# source_eagle.net
KiCad netlist of a schematic drawn in EAGLE
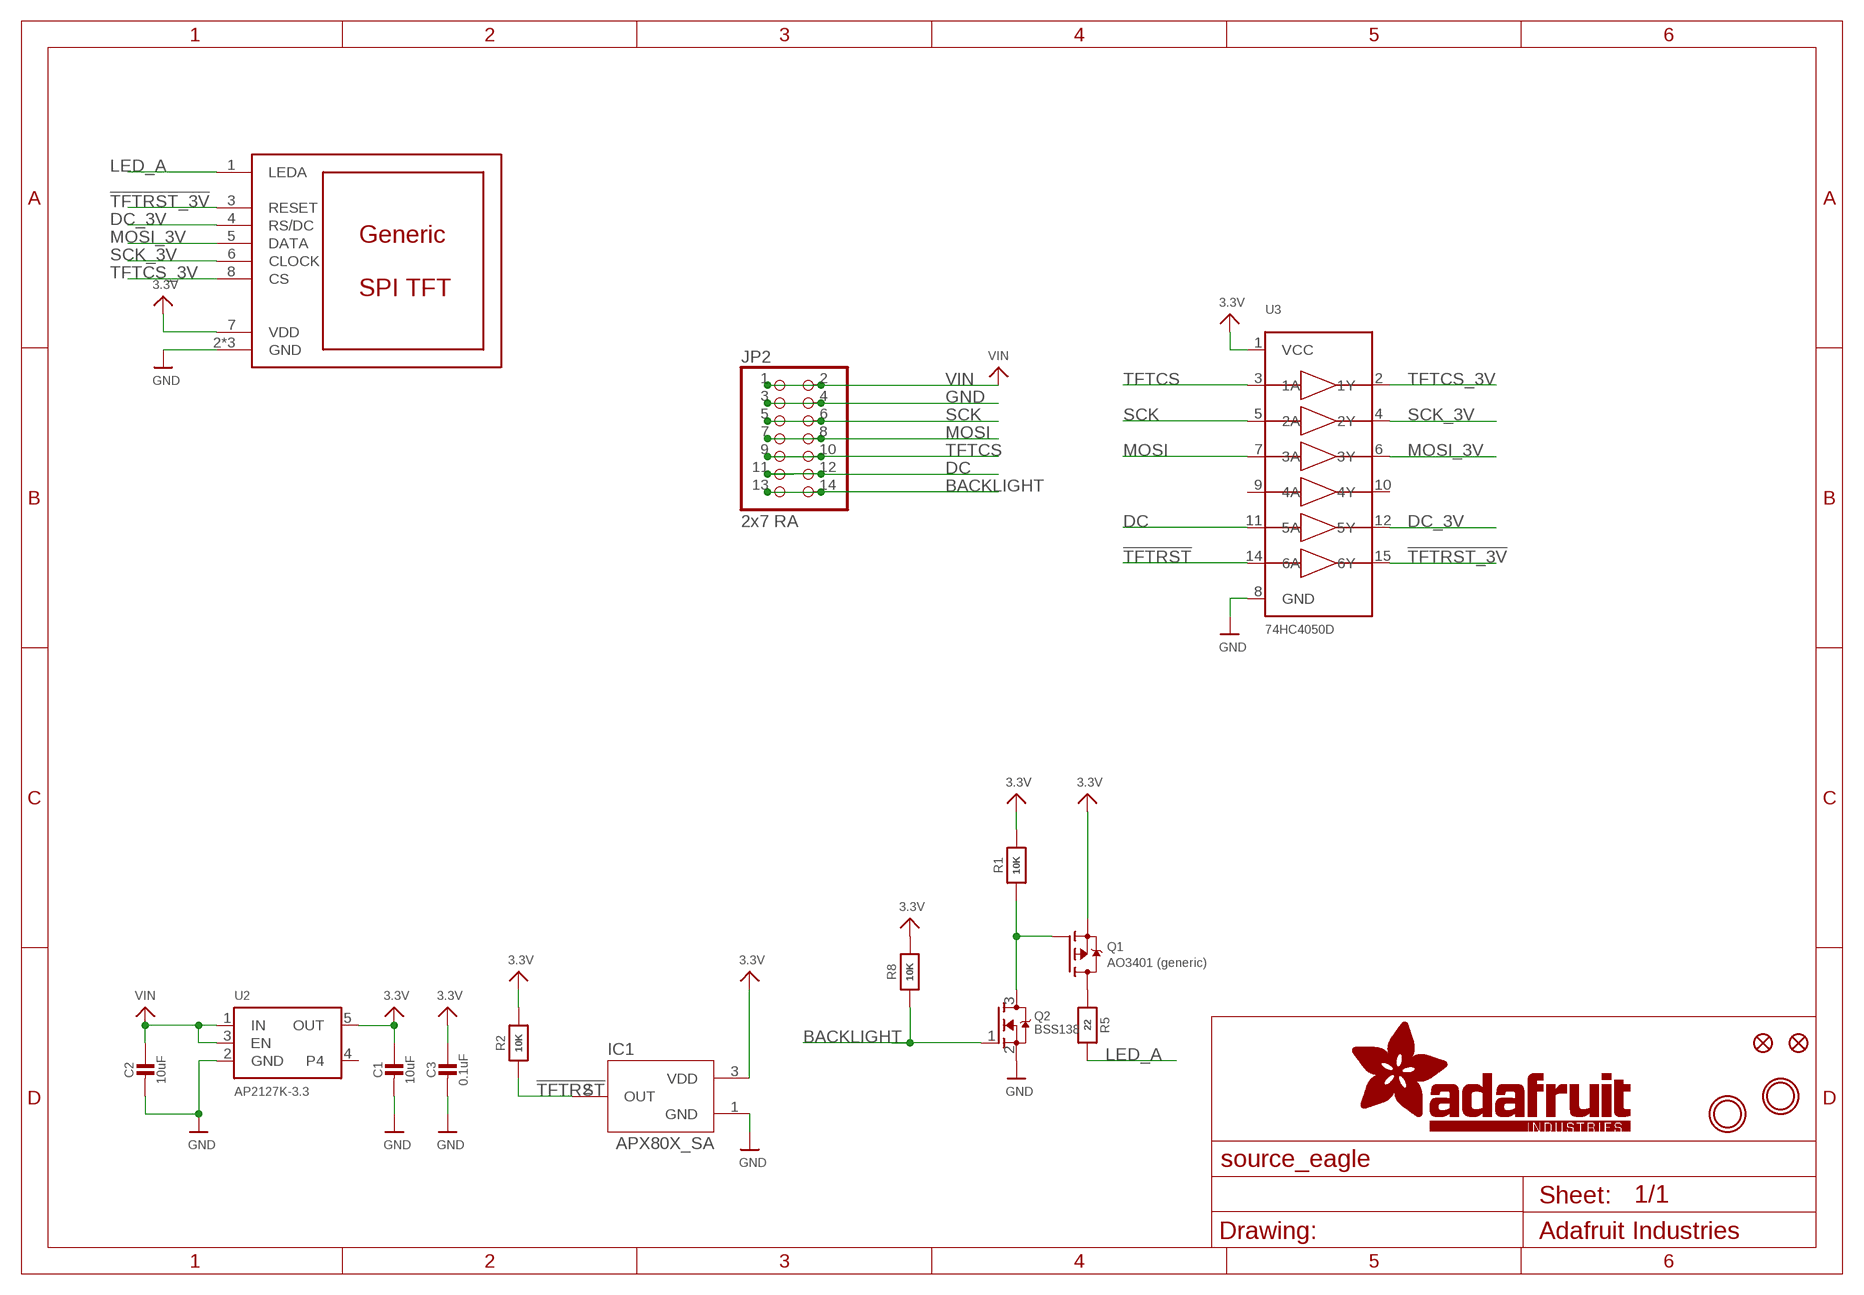
[diagram p0: schematic, sheet 1]

(export (version "E")
  (design (tool "Eeschema 10.0.6"))
  (components
    (comp (ref "C1")
      (value "10uF")
      (footprint "eagle-import:0805-NO")
      (libsource (lib "eagle-import") (part "CAP_CERAMIC0805-NOOUTLINE"))
    )
    (comp (ref "C2")
      (value "10uF")
      (footprint "eagle-import:0805-NO")
      (libsource (lib "eagle-import") (part "CAP_CERAMIC0805-NOOUTLINE"))
    )
    (comp (ref "C3")
      (value "0.1uF")
      (footprint "eagle-import:0603-NO")
      (libsource (lib "eagle-import") (part "CAP_CERAMIC0603_NO"))
    )
    (comp (ref "DISP2")
      (value "DISP_LCD_GENERIC_SPI_NOLEDA_1.14_240X135_FPC")
      (footprint "eagle-import:TFT_1.14IN_240X135_FPC")
      (libsource (lib "eagle-import") (part "DISP_LCD_GENERIC_SPI_NOLEDA_1.14_240X135_FPC"))
    )
    (comp (ref "FID1")
      (value "FIDUCIAL_1MM")
      (footprint "eagle-import:FIDUCIAL_1MM")
      (libsource (lib "eagle-import") (part "FIDUCIAL_1MM"))
    )
    (comp (ref "FID2")
      (value "FIDUCIAL_1MM")
      (footprint "eagle-import:FIDUCIAL_1MM")
      (libsource (lib "eagle-import") (part "FIDUCIAL_1MM"))
    )
    (comp (ref "IC1")
      (value "APX80X_SA")
      (footprint "eagle-import:SOT23-WIDE")
      (libsource (lib "eagle-import") (part "RESET_SUPERVISORAPX80X_SA"))
    )
    (comp (ref "JP2")
      (value "2x7 RA")
      (footprint "eagle-import:2X07_ROUND_70MIL")
      (libsource (lib "eagle-import") (part "HEADER-2X7_ROUND_70MIL"))
    )
    (comp (ref "Q1")
      (value "AO3401 (generic)")
      (footprint "eagle-import:SOT23-WIDE")
      (libsource (lib "eagle-import") (part "MOSFET-PWIDE"))
    )
    (comp (ref "Q2")
      (value "BSS138")
      (footprint "eagle-import:SOT23-WIDE")
      (libsource (lib "eagle-import") (part "MOSFET-NWIDE"))
    )
    (comp (ref "R1")
      (value "10K")
      (footprint "eagle-import:0603-NO")
      (libsource (lib "eagle-import") (part "RESISTOR_0603_NOOUT"))
    )
    (comp (ref "R2")
      (value "10K")
      (footprint "eagle-import:0603-NO")
      (libsource (lib "eagle-import") (part "RESISTOR_0603_NOOUT"))
    )
    (comp (ref "R5")
      (value "22")
      (footprint "eagle-import:0603-NO")
      (libsource (lib "eagle-import") (part "RESISTOR_0603_NOOUT"))
    )
    (comp (ref "R8")
      (value "10K")
      (footprint "eagle-import:0603-NO")
      (libsource (lib "eagle-import") (part "RESISTOR_0603_NOOUT"))
    )
    (comp (ref "U$9")
      (value "MOUNTINGHOLE2.5")
      (footprint "eagle-import:MOUNTINGHOLE_2.5_PLATED")
      (libsource (lib "eagle-import") (part "MOUNTINGHOLE2.5"))
    )
    (comp (ref "U$10")
      (value "MOUNTINGHOLE2.5")
      (footprint "eagle-import:MOUNTINGHOLE_2.5_PLATED")
      (libsource (lib "eagle-import") (part "MOUNTINGHOLE2.5"))
    )
    (comp (ref "U2")
      (value "AP2127K-3.3")
      (footprint "eagle-import:SOT23-5")
      (libsource (lib "eagle-import") (part "VREG_SOT23-5"))
    )
    (comp (ref "U3")
      (value "74HC4050D")
      (footprint "eagle-import:TSSOP16")
      (libsource (lib "eagle-import") (part "74HC4050DTSSOP"))
    )
  )
  (nets
    (net (code "1") (name "/BACKLIGHT") (class "Default")
      (node (ref "JP2") (pin "13") (pinfunction "13_13") (pintype "passive"))
      (node (ref "JP2") (pin "14") (pinfunction "14_14") (pintype "passive"))
      (node (ref "Q2") (pin "1") (pinfunction "G_1") (pintype "bidirectional"))
      (node (ref "R8") (pin "1") (pinfunction "1_1") (pintype "passive"))
    )
    (net (code "2") (name "/DC") (class "Default")
      (node (ref "JP2") (pin "11") (pinfunction "11_11") (pintype "passive"))
      (node (ref "JP2") (pin "12") (pinfunction "12_12") (pintype "passive"))
      (node (ref "U3") (pin "11") (pinfunction "5A_11") (pintype "bidirectional"))
    )
    (net (code "3") (name "/DC_3V") (class "Default")
      (node (ref "DISP2") (pin "4") (pinfunction "RS/DC_4") (pintype "input"))
      (node (ref "U3") (pin "12") (pinfunction "5Y_12") (pintype "bidirectional"))
    )
    (net (code "4") (name "/LED_A") (class "Default")
      (node (ref "DISP2") (pin "1") (pinfunction "LEDA_1") (pintype "input"))
      (node (ref "R5") (pin "2") (pinfunction "2_2") (pintype "passive"))
    )
    (net (code "5") (name "/MOSI") (class "Default")
      (node (ref "JP2") (pin "7") (pinfunction "7_7") (pintype "passive"))
      (node (ref "JP2") (pin "8") (pinfunction "8_8") (pintype "passive"))
      (node (ref "U3") (pin "7") (pinfunction "3A_7") (pintype "bidirectional"))
    )
    (net (code "6") (name "/MOSI_3V") (class "Default")
      (node (ref "DISP2") (pin "5") (pinfunction "DATA_5") (pintype "bidirectional"))
      (node (ref "U3") (pin "6") (pinfunction "3Y_6") (pintype "bidirectional"))
    )
    (net (code "7") (name "/SCK") (class "Default")
      (node (ref "JP2") (pin "5") (pinfunction "5_5") (pintype "passive"))
      (node (ref "JP2") (pin "6") (pinfunction "6_6") (pintype "passive"))
      (node (ref "U3") (pin "5") (pinfunction "2A_5") (pintype "bidirectional"))
    )
    (net (code "8") (name "/SCK_3V") (class "Default")
      (node (ref "DISP2") (pin "6") (pinfunction "CLOCK_6") (pintype "input"))
      (node (ref "U3") (pin "4") (pinfunction "2Y_4") (pintype "bidirectional"))
    )
    (net (code "9") (name "/TFTCS") (class "Default")
      (node (ref "JP2") (pin "10") (pinfunction "10_10") (pintype "passive"))
      (node (ref "JP2") (pin "9") (pinfunction "9_9") (pintype "passive"))
      (node (ref "U3") (pin "3") (pinfunction "1A_3") (pintype "bidirectional"))
    )
    (net (code "10") (name "/TFTCS_3V") (class "Default")
      (node (ref "DISP2") (pin "8") (pinfunction "CS_8") (pintype "input"))
      (node (ref "U3") (pin "2") (pinfunction "1Y_2") (pintype "bidirectional"))
    )
    (net (code "11") (name "/~{TFTRST_3V}") (class "Default")
      (node (ref "DISP2") (pin "3") (pinfunction "RESET_3") (pintype "input"))
      (node (ref "U3") (pin "15") (pinfunction "6Y_15") (pintype "bidirectional"))
    )
    (net (code "12") (name "/~{TFTRST}") (class "Default")
      (node (ref "IC1") (pin "2") (pinfunction "OUT_2") (pintype "output"))
      (node (ref "R2") (pin "1") (pinfunction "1_1") (pintype "passive"))
      (node (ref "U3") (pin "14") (pinfunction "6A_14") (pintype "bidirectional"))
    )
    (net (code "13") (name "3.3V") (class "Default")
      (node (ref "C1") (pin "1") (pinfunction "1_1") (pintype "passive"))
      (node (ref "C3") (pin "1") (pinfunction "1_1") (pintype "passive"))
      (node (ref "DISP2") (pin "7") (pinfunction "VDD_7") (pintype "power_in"))
      (node (ref "IC1") (pin "3") (pinfunction "VDD_3") (pintype "power_in"))
      (node (ref "Q1") (pin "2") (pinfunction "S_2") (pintype "passive"))
      (node (ref "R1") (pin "2") (pinfunction "2_2") (pintype "passive"))
      (node (ref "R2") (pin "2") (pinfunction "2_2") (pintype "passive"))
      (node (ref "R8") (pin "2") (pinfunction "2_2") (pintype "passive"))
      (node (ref "U2") (pin "5") (pinfunction "OUT_5") (pintype "power_in"))
      (node (ref "U3") (pin "1") (pinfunction "VCC_1") (pintype "bidirectional"))
    )
    (net (code "14") (name "GND") (class "Default")
      (node (ref "C1") (pin "2") (pinfunction "2_2") (pintype "passive"))
      (node (ref "C2") (pin "2") (pinfunction "2_2") (pintype "passive"))
      (node (ref "C3") (pin "2") (pinfunction "2_2") (pintype "passive"))
      (node (ref "DISP2") (pin "2") (pinfunction "GND_2") (pintype "power_in"))
      (node (ref "DISP2") (pin "MT1") (pinfunction "GND_MT1") (pintype "power_in"))
      (node (ref "DISP2") (pin "MT2") (pinfunction "GND_MT2") (pintype "power_in"))
      (node (ref "IC1") (pin "1") (pinfunction "GND_1") (pintype "power_in"))
      (node (ref "JP2") (pin "3") (pinfunction "3_3") (pintype "passive"))
      (node (ref "JP2") (pin "4") (pinfunction "4_4") (pintype "passive"))
      (node (ref "Q2") (pin "2") (pinfunction "S_2") (pintype "bidirectional"))
      (node (ref "U2") (pin "2") (pinfunction "GND_2") (pintype "power_in"))
      (node (ref "U3") (pin "8") (pinfunction "GND_8") (pintype "bidirectional"))
    )
    (net (code "15") (name "Net-(Q1-D)") (class "Default")
      (node (ref "Q1") (pin "3") (pinfunction "D_3") (pintype "passive"))
      (node (ref "R5") (pin "1") (pinfunction "1_1") (pintype "passive"))
    )
    (net (code "16") (name "Net-(Q1-G)") (class "Default")
      (node (ref "Q1") (pin "1") (pinfunction "G_1") (pintype "passive"))
      (node (ref "Q2") (pin "3") (pinfunction "D_3") (pintype "bidirectional"))
      (node (ref "R1") (pin "1") (pinfunction "1_1") (pintype "passive"))
    )
    (net (code "17") (name "VIN") (class "Default")
      (node (ref "C2") (pin "1") (pinfunction "1_1") (pintype "passive"))
      (node (ref "JP2") (pin "1") (pinfunction "1_1") (pintype "passive"))
      (node (ref "JP2") (pin "2") (pinfunction "2_2") (pintype "passive"))
      (node (ref "U2") (pin "1") (pinfunction "IN_1") (pintype "power_in"))
      (node (ref "U2") (pin "3") (pinfunction "EN_3") (pintype "input"))
    )
    (net (code "18") (name "unconnected-(U2-P4-Pad4)") (class "Default")
      (node (ref "U2") (pin "4") (pinfunction "P4_4") (pintype "bidirectional"))
    )
    (net (code "19") (name "unconnected-(U3-4A-Pad9)") (class "Default")
      (node (ref "U3") (pin "9") (pinfunction "4A_9") (pintype "bidirectional"))
    )
    (net (code "20") (name "unconnected-(U3-4Y-Pad10)") (class "Default")
      (node (ref "U3") (pin "10") (pinfunction "4Y_10") (pintype "bidirectional"))
    )
  )
)
